# 1-10.net
KiCad netlist of a schematic drawn in EAGLE
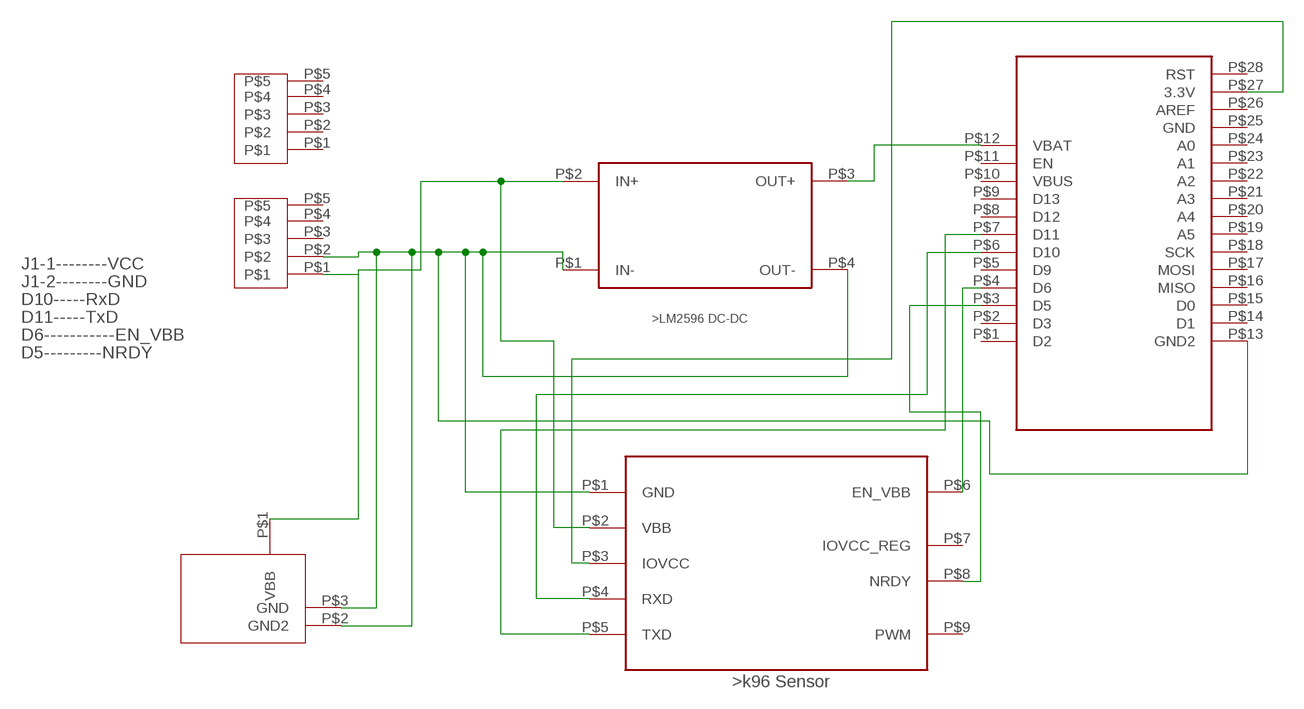
[diagram p0: schematic, sheet 1]

(export (version "E")
  (design (tool "Eeschema 10.0.6"))
  (components
    (comp (ref "DCDC1")
      (value "DCDC")
      (footprint "eagle-import:DCDC")
      (libsource (lib "eagle-import") (part "DCDC"))
    )
    (comp (ref "FEATHER1")
      (value "FEATHER")
      (footprint "eagle-import:FEATHER")
      (libsource (lib "eagle-import") (part "FEATHER"))
    )
    (comp (ref "K96SENSOR1")
      (value "K96SENSOR")
      (footprint "eagle-import:K96SENSOR")
      (libsource (lib "eagle-import") (part "K96SENSOR"))
    )
    (comp (ref "PIN1")
      (value "PIN")
      (footprint "eagle-import:PIN")
      (libsource (lib "eagle-import") (part "PIN"))
    )
    (comp (ref "PIN2")
      (value "PIN")
      (footprint "eagle-import:PIN")
      (libsource (lib "eagle-import") (part "PIN"))
    )
    (comp (ref "U$1")
      (value "POWER")
      (footprint "eagle-import:POWERIN")
      (libsource (lib "eagle-import") (part "POWER"))
    )
  )
  (nets
    (net (code "1") (name "Net-(DCDC1-IN+)") (class "Default")
      (node (ref "DCDC1") (pin "P$2") (pinfunction "IN+_P$2") (pintype "bidirectional"))
      (node (ref "K96SENSOR1") (pin "P$2") (pinfunction "VBB_P$2") (pintype "bidirectional"))
      (node (ref "PIN1") (pin "P$1") (pinfunction "P$1_P$1") (pintype "bidirectional"))
      (node (ref "U$1") (pin "P$1") (pinfunction "VBB_P$1") (pintype "bidirectional"))
    )
    (net (code "2") (name "Net-(DCDC1-IN-)") (class "Default")
      (node (ref "DCDC1") (pin "P$1") (pinfunction "IN-_P$1") (pintype "bidirectional"))
      (node (ref "DCDC1") (pin "P$4") (pinfunction "OUT-_P$4") (pintype "bidirectional"))
      (node (ref "FEATHER1") (pin "P$13") (pinfunction "GND2_P$13") (pintype "bidirectional"))
      (node (ref "K96SENSOR1") (pin "P$1") (pinfunction "GND_P$1") (pintype "bidirectional"))
      (node (ref "PIN1") (pin "P$2") (pinfunction "P$2_P$2") (pintype "bidirectional"))
      (node (ref "U$1") (pin "P$2") (pinfunction "GND2_P$2") (pintype "bidirectional"))
      (node (ref "U$1") (pin "P$3") (pinfunction "GND_P$3") (pintype "bidirectional"))
    )
    (net (code "3") (name "Net-(DCDC1-OUT+)") (class "Default")
      (node (ref "DCDC1") (pin "P$3") (pinfunction "OUT+_P$3") (pintype "bidirectional"))
      (node (ref "FEATHER1") (pin "P$12") (pinfunction "VBAT_P$12") (pintype "bidirectional"))
    )
    (net (code "4") (name "Net-(FEATHER1-3.3V)") (class "Default")
      (node (ref "FEATHER1") (pin "P$27") (pinfunction "3.3V_P$27") (pintype "bidirectional"))
      (node (ref "K96SENSOR1") (pin "P$3") (pinfunction "IOVCC_P$3") (pintype "bidirectional"))
    )
    (net (code "5") (name "Net-(FEATHER1-D5)") (class "Default")
      (node (ref "FEATHER1") (pin "P$3") (pinfunction "D5_P$3") (pintype "bidirectional"))
      (node (ref "K96SENSOR1") (pin "P$8") (pinfunction "NRDY_P$8") (pintype "bidirectional"))
    )
    (net (code "6") (name "Net-(FEATHER1-D6)") (class "Default")
      (node (ref "FEATHER1") (pin "P$4") (pinfunction "D6_P$4") (pintype "bidirectional"))
      (node (ref "K96SENSOR1") (pin "P$6") (pinfunction "EN_VBB_P$6") (pintype "bidirectional"))
    )
    (net (code "7") (name "Net-(FEATHER1-D10)") (class "Default")
      (node (ref "FEATHER1") (pin "P$6") (pinfunction "D10_P$6") (pintype "bidirectional"))
      (node (ref "K96SENSOR1") (pin "P$4") (pinfunction "RXD_P$4") (pintype "bidirectional"))
    )
    (net (code "8") (name "Net-(FEATHER1-D11)") (class "Default")
      (node (ref "FEATHER1") (pin "P$7") (pinfunction "D11_P$7") (pintype "bidirectional"))
      (node (ref "K96SENSOR1") (pin "P$5") (pinfunction "TXD_P$5") (pintype "bidirectional"))
    )
    (net (code "9") (name "unconnected-(FEATHER1-A0-PadP$24)") (class "Default")
      (node (ref "FEATHER1") (pin "P$24") (pinfunction "A0_P$24") (pintype "bidirectional"))
    )
    (net (code "10") (name "unconnected-(FEATHER1-A1-PadP$23)") (class "Default")
      (node (ref "FEATHER1") (pin "P$23") (pinfunction "A1_P$23") (pintype "bidirectional"))
    )
    (net (code "11") (name "unconnected-(FEATHER1-A2-PadP$22)") (class "Default")
      (node (ref "FEATHER1") (pin "P$22") (pinfunction "A2_P$22") (pintype "bidirectional"))
    )
    (net (code "12") (name "unconnected-(FEATHER1-A3-PadP$21)") (class "Default")
      (node (ref "FEATHER1") (pin "P$21") (pinfunction "A3_P$21") (pintype "bidirectional"))
    )
    (net (code "13") (name "unconnected-(FEATHER1-A4-PadP$20)") (class "Default")
      (node (ref "FEATHER1") (pin "P$20") (pinfunction "A4_P$20") (pintype "bidirectional"))
    )
    (net (code "14") (name "unconnected-(FEATHER1-A5-PadP$19)") (class "Default")
      (node (ref "FEATHER1") (pin "P$19") (pinfunction "A5_P$19") (pintype "bidirectional"))
    )
    (net (code "15") (name "unconnected-(FEATHER1-AREF-PadP$26)") (class "Default")
      (node (ref "FEATHER1") (pin "P$26") (pinfunction "AREF_P$26") (pintype "bidirectional"))
    )
    (net (code "16") (name "unconnected-(FEATHER1-D0-PadP$15)") (class "Default")
      (node (ref "FEATHER1") (pin "P$15") (pinfunction "D0_P$15") (pintype "bidirectional"))
    )
    (net (code "17") (name "unconnected-(FEATHER1-D1-PadP$14)") (class "Default")
      (node (ref "FEATHER1") (pin "P$14") (pinfunction "D1_P$14") (pintype "bidirectional"))
    )
    (net (code "18") (name "unconnected-(FEATHER1-D2-PadP$1)") (class "Default")
      (node (ref "FEATHER1") (pin "P$1") (pinfunction "D2_P$1") (pintype "bidirectional"))
    )
    (net (code "19") (name "unconnected-(FEATHER1-D3-PadP$2)") (class "Default")
      (node (ref "FEATHER1") (pin "P$2") (pinfunction "D3_P$2") (pintype "bidirectional"))
    )
    (net (code "20") (name "unconnected-(FEATHER1-D9-PadP$5)") (class "Default")
      (node (ref "FEATHER1") (pin "P$5") (pinfunction "D9_P$5") (pintype "bidirectional"))
    )
    (net (code "21") (name "unconnected-(FEATHER1-D12-PadP$8)") (class "Default")
      (node (ref "FEATHER1") (pin "P$8") (pinfunction "D12_P$8") (pintype "bidirectional"))
    )
    (net (code "22") (name "unconnected-(FEATHER1-D13-PadP$9)") (class "Default")
      (node (ref "FEATHER1") (pin "P$9") (pinfunction "D13_P$9") (pintype "bidirectional"))
    )
    (net (code "23") (name "unconnected-(FEATHER1-EN-PadP$11)") (class "Default")
      (node (ref "FEATHER1") (pin "P$11") (pinfunction "EN_P$11") (pintype "bidirectional"))
    )
    (net (code "24") (name "unconnected-(FEATHER1-GND-PadP$25)") (class "Default")
      (node (ref "FEATHER1") (pin "P$25") (pinfunction "GND_P$25") (pintype "bidirectional"))
    )
    (net (code "25") (name "unconnected-(FEATHER1-MISO-PadP$16)") (class "Default")
      (node (ref "FEATHER1") (pin "P$16") (pinfunction "MISO_P$16") (pintype "bidirectional"))
    )
    (net (code "26") (name "unconnected-(FEATHER1-MOSI-PadP$17)") (class "Default")
      (node (ref "FEATHER1") (pin "P$17") (pinfunction "MOSI_P$17") (pintype "bidirectional"))
    )
    (net (code "27") (name "unconnected-(FEATHER1-RST-PadP$28)") (class "Default")
      (node (ref "FEATHER1") (pin "P$28") (pinfunction "RST_P$28") (pintype "bidirectional"))
    )
    (net (code "28") (name "unconnected-(FEATHER1-SCK-PadP$18)") (class "Default")
      (node (ref "FEATHER1") (pin "P$18") (pinfunction "SCK_P$18") (pintype "bidirectional"))
    )
    (net (code "29") (name "unconnected-(FEATHER1-VBUS-PadP$10)") (class "Default")
      (node (ref "FEATHER1") (pin "P$10") (pinfunction "VBUS_P$10") (pintype "bidirectional"))
    )
    (net (code "30") (name "unconnected-(K96SENSOR1-IOVCC_REG-PadP$7)") (class "Default")
      (node (ref "K96SENSOR1") (pin "P$7") (pinfunction "IOVCC_REG_P$7") (pintype "bidirectional"))
    )
    (net (code "31") (name "unconnected-(K96SENSOR1-PWM-PadP$9)") (class "Default")
      (node (ref "K96SENSOR1") (pin "P$9") (pinfunction "PWM_P$9") (pintype "bidirectional"))
    )
    (net (code "32") (name "unconnected-(PIN1-PadP$3)") (class "Default")
      (node (ref "PIN1") (pin "P$3") (pinfunction "P$3_P$3") (pintype "bidirectional"))
    )
    (net (code "33") (name "unconnected-(PIN1-PadP$4)") (class "Default")
      (node (ref "PIN1") (pin "P$4") (pinfunction "P$4_P$4") (pintype "bidirectional"))
    )
    (net (code "34") (name "unconnected-(PIN1-PadP$5)") (class "Default")
      (node (ref "PIN1") (pin "P$5") (pinfunction "P$5_P$5") (pintype "bidirectional"))
    )
    (net (code "35") (name "unconnected-(PIN2-PadP$1)") (class "Default")
      (node (ref "PIN2") (pin "P$1") (pinfunction "P$1_P$1") (pintype "bidirectional"))
    )
    (net (code "36") (name "unconnected-(PIN2-PadP$2)") (class "Default")
      (node (ref "PIN2") (pin "P$2") (pinfunction "P$2_P$2") (pintype "bidirectional"))
    )
    (net (code "37") (name "unconnected-(PIN2-PadP$3)") (class "Default")
      (node (ref "PIN2") (pin "P$3") (pinfunction "P$3_P$3") (pintype "bidirectional"))
    )
    (net (code "38") (name "unconnected-(PIN2-PadP$4)") (class "Default")
      (node (ref "PIN2") (pin "P$4") (pinfunction "P$4_P$4") (pintype "bidirectional"))
    )
    (net (code "39") (name "unconnected-(PIN2-PadP$5)") (class "Default")
      (node (ref "PIN2") (pin "P$5") (pinfunction "P$5_P$5") (pintype "bidirectional"))
    )
  )
)
